# breakout.net
KiCad netlist of a schematic drawn in EAGLE
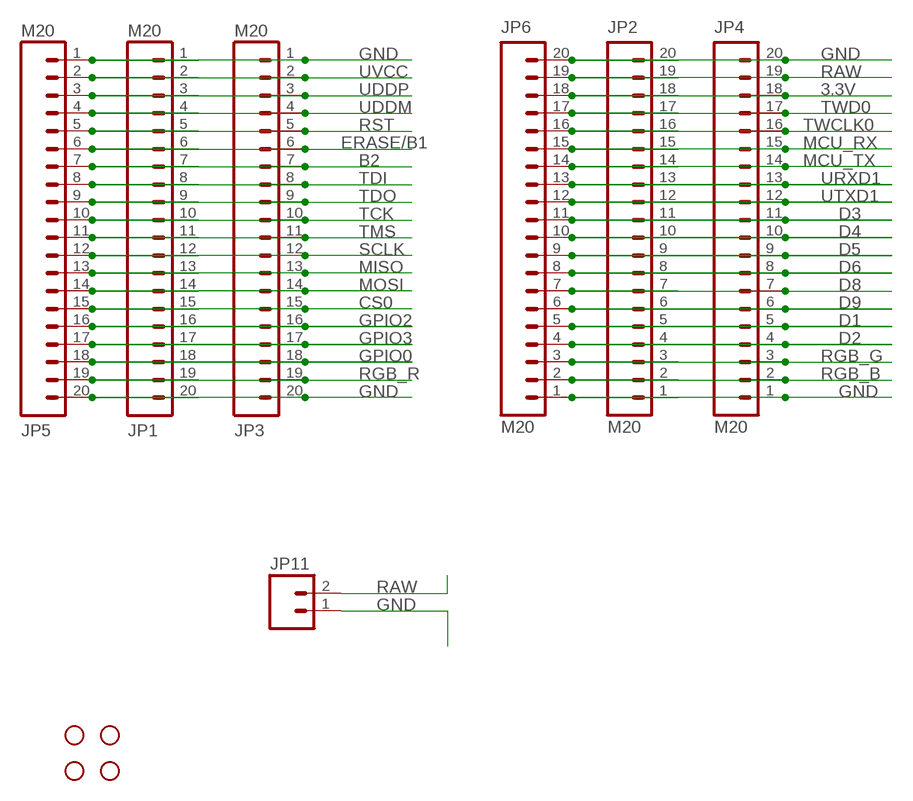
[diagram p0: schematic, sheet 1]

(export (version "E")
  (design (tool "Eeschema 10.0.6"))
  (components
    (comp (ref "JP1")
      (value "M20")
      (footprint "eagle-import:1X20")
      (libsource (lib "eagle-import") (part "M20"))
    )
    (comp (ref "JP2")
      (value "M20")
      (footprint "eagle-import:1X20")
      (libsource (lib "eagle-import") (part "M20"))
    )
    (comp (ref "JP3")
      (value "M20")
      (footprint "eagle-import:1X20")
      (libsource (lib "eagle-import") (part "M20"))
    )
    (comp (ref "JP4")
      (value "M20")
      (footprint "eagle-import:1X20")
      (libsource (lib "eagle-import") (part "M20"))
    )
    (comp (ref "JP5")
      (value "M20")
      (footprint "eagle-import:1X20")
      (libsource (lib "eagle-import") (part "M20"))
    )
    (comp (ref "JP6")
      (value "M20")
      (footprint "eagle-import:1X20")
      (libsource (lib "eagle-import") (part "M20"))
    )
    (comp (ref "JP7")
      (value "STAND-OFF")
      (footprint "eagle-import:STAND-OFF")
      (libsource (lib "eagle-import") (part "STAND-OFF"))
    )
    (comp (ref "JP8")
      (value "STAND-OFF")
      (footprint "eagle-import:STAND-OFF")
      (libsource (lib "eagle-import") (part "STAND-OFF"))
    )
    (comp (ref "JP9")
      (value "STAND-OFF")
      (footprint "eagle-import:STAND-OFF")
      (libsource (lib "eagle-import") (part "STAND-OFF"))
    )
    (comp (ref "JP10")
      (value "STAND-OFF")
      (footprint "eagle-import:STAND-OFF")
      (libsource (lib "eagle-import") (part "STAND-OFF"))
    )
    (comp (ref "JP11")
      (value "M02JST-PTH-2")
      (footprint "eagle-import:JST-2-PTH")
      (libsource (lib "eagle-import") (part "M02JST-PTH-2"))
    )
  )
  (nets
    (net (code "1") (name "3.3V") (class "Default")
      (node (ref "JP2") (pin "18") (pinfunction "18_18") (pintype "passive"))
      (node (ref "JP4") (pin "18") (pinfunction "18_18") (pintype "passive"))
      (node (ref "JP6") (pin "18") (pinfunction "18_18") (pintype "passive"))
    )
    (net (code "2") (name "B2") (class "Default")
      (node (ref "JP1") (pin "7") (pinfunction "7_7") (pintype "passive"))
      (node (ref "JP3") (pin "7") (pinfunction "7_7") (pintype "passive"))
      (node (ref "JP5") (pin "7") (pinfunction "7_7") (pintype "passive"))
    )
    (net (code "3") (name "CS0") (class "Default")
      (node (ref "JP1") (pin "15") (pinfunction "15_15") (pintype "passive"))
      (node (ref "JP3") (pin "15") (pinfunction "15_15") (pintype "passive"))
      (node (ref "JP5") (pin "15") (pinfunction "15_15") (pintype "passive"))
    )
    (net (code "4") (name "D1") (class "Default")
      (node (ref "JP2") (pin "5") (pinfunction "5_5") (pintype "passive"))
      (node (ref "JP4") (pin "5") (pinfunction "5_5") (pintype "passive"))
      (node (ref "JP6") (pin "5") (pinfunction "5_5") (pintype "passive"))
    )
    (net (code "5") (name "D2") (class "Default")
      (node (ref "JP2") (pin "4") (pinfunction "4_4") (pintype "passive"))
      (node (ref "JP4") (pin "4") (pinfunction "4_4") (pintype "passive"))
      (node (ref "JP6") (pin "4") (pinfunction "4_4") (pintype "passive"))
    )
    (net (code "6") (name "D3") (class "Default")
      (node (ref "JP2") (pin "11") (pinfunction "11_11") (pintype "passive"))
      (node (ref "JP4") (pin "11") (pinfunction "11_11") (pintype "passive"))
      (node (ref "JP6") (pin "11") (pinfunction "11_11") (pintype "passive"))
    )
    (net (code "7") (name "D4") (class "Default")
      (node (ref "JP2") (pin "10") (pinfunction "10_10") (pintype "passive"))
      (node (ref "JP4") (pin "10") (pinfunction "10_10") (pintype "passive"))
      (node (ref "JP6") (pin "10") (pinfunction "10_10") (pintype "passive"))
    )
    (net (code "8") (name "D5") (class "Default")
      (node (ref "JP2") (pin "9") (pinfunction "9_9") (pintype "passive"))
      (node (ref "JP4") (pin "9") (pinfunction "9_9") (pintype "passive"))
      (node (ref "JP6") (pin "9") (pinfunction "9_9") (pintype "passive"))
    )
    (net (code "9") (name "D6") (class "Default")
      (node (ref "JP2") (pin "8") (pinfunction "8_8") (pintype "passive"))
      (node (ref "JP4") (pin "8") (pinfunction "8_8") (pintype "passive"))
      (node (ref "JP6") (pin "8") (pinfunction "8_8") (pintype "passive"))
    )
    (net (code "10") (name "D8") (class "Default")
      (node (ref "JP2") (pin "7") (pinfunction "7_7") (pintype "passive"))
      (node (ref "JP4") (pin "7") (pinfunction "7_7") (pintype "passive"))
      (node (ref "JP6") (pin "7") (pinfunction "7_7") (pintype "passive"))
    )
    (net (code "11") (name "D9") (class "Default")
      (node (ref "JP2") (pin "6") (pinfunction "6_6") (pintype "passive"))
      (node (ref "JP4") (pin "6") (pinfunction "6_6") (pintype "passive"))
      (node (ref "JP6") (pin "6") (pinfunction "6_6") (pintype "passive"))
    )
    (net (code "12") (name "ERASE{slash}B1") (class "Default")
      (node (ref "JP1") (pin "6") (pinfunction "6_6") (pintype "passive"))
      (node (ref "JP3") (pin "6") (pinfunction "6_6") (pintype "passive"))
      (node (ref "JP5") (pin "6") (pinfunction "6_6") (pintype "passive"))
    )
    (net (code "13") (name "GND") (class "Default")
      (node (ref "JP1") (pin "1") (pinfunction "1_1") (pintype "passive"))
      (node (ref "JP1") (pin "20") (pinfunction "20_20") (pintype "passive"))
      (node (ref "JP11") (pin "1") (pinfunction "1_1") (pintype "passive"))
      (node (ref "JP2") (pin "1") (pinfunction "1_1") (pintype "passive"))
      (node (ref "JP2") (pin "20") (pinfunction "20_20") (pintype "passive"))
      (node (ref "JP3") (pin "1") (pinfunction "1_1") (pintype "passive"))
      (node (ref "JP3") (pin "20") (pinfunction "20_20") (pintype "passive"))
      (node (ref "JP4") (pin "1") (pinfunction "1_1") (pintype "passive"))
      (node (ref "JP4") (pin "20") (pinfunction "20_20") (pintype "passive"))
      (node (ref "JP5") (pin "1") (pinfunction "1_1") (pintype "passive"))
      (node (ref "JP5") (pin "20") (pinfunction "20_20") (pintype "passive"))
      (node (ref "JP6") (pin "1") (pinfunction "1_1") (pintype "passive"))
      (node (ref "JP6") (pin "20") (pinfunction "20_20") (pintype "passive"))
    )
    (net (code "14") (name "GPIO0") (class "Default")
      (node (ref "JP1") (pin "18") (pinfunction "18_18") (pintype "passive"))
      (node (ref "JP3") (pin "18") (pinfunction "18_18") (pintype "passive"))
      (node (ref "JP5") (pin "18") (pinfunction "18_18") (pintype "passive"))
    )
    (net (code "15") (name "GPIO2") (class "Default")
      (node (ref "JP1") (pin "16") (pinfunction "16_16") (pintype "passive"))
      (node (ref "JP3") (pin "16") (pinfunction "16_16") (pintype "passive"))
      (node (ref "JP5") (pin "16") (pinfunction "16_16") (pintype "passive"))
    )
    (net (code "16") (name "GPIO3") (class "Default")
      (node (ref "JP1") (pin "17") (pinfunction "17_17") (pintype "passive"))
      (node (ref "JP3") (pin "17") (pinfunction "17_17") (pintype "passive"))
      (node (ref "JP5") (pin "17") (pinfunction "17_17") (pintype "passive"))
    )
    (net (code "17") (name "MCU_RX") (class "Default")
      (node (ref "JP2") (pin "15") (pinfunction "15_15") (pintype "passive"))
      (node (ref "JP4") (pin "15") (pinfunction "15_15") (pintype "passive"))
      (node (ref "JP6") (pin "15") (pinfunction "15_15") (pintype "passive"))
    )
    (net (code "18") (name "MCU_TX") (class "Default")
      (node (ref "JP2") (pin "14") (pinfunction "14_14") (pintype "passive"))
      (node (ref "JP4") (pin "14") (pinfunction "14_14") (pintype "passive"))
      (node (ref "JP6") (pin "14") (pinfunction "14_14") (pintype "passive"))
    )
    (net (code "19") (name "MISO") (class "Default")
      (node (ref "JP1") (pin "13") (pinfunction "13_13") (pintype "passive"))
      (node (ref "JP3") (pin "13") (pinfunction "13_13") (pintype "passive"))
      (node (ref "JP5") (pin "13") (pinfunction "13_13") (pintype "passive"))
    )
    (net (code "20") (name "MOSI") (class "Default")
      (node (ref "JP1") (pin "14") (pinfunction "14_14") (pintype "passive"))
      (node (ref "JP3") (pin "14") (pinfunction "14_14") (pintype "passive"))
      (node (ref "JP5") (pin "14") (pinfunction "14_14") (pintype "passive"))
    )
    (net (code "21") (name "RAW") (class "Default")
      (node (ref "JP11") (pin "2") (pinfunction "2_2") (pintype "passive"))
      (node (ref "JP2") (pin "19") (pinfunction "19_19") (pintype "passive"))
      (node (ref "JP4") (pin "19") (pinfunction "19_19") (pintype "passive"))
      (node (ref "JP6") (pin "19") (pinfunction "19_19") (pintype "passive"))
    )
    (net (code "22") (name "RGB_B") (class "Default")
      (node (ref "JP2") (pin "2") (pinfunction "2_2") (pintype "passive"))
      (node (ref "JP4") (pin "2") (pinfunction "2_2") (pintype "passive"))
      (node (ref "JP6") (pin "2") (pinfunction "2_2") (pintype "passive"))
    )
    (net (code "23") (name "RGB_G") (class "Default")
      (node (ref "JP2") (pin "3") (pinfunction "3_3") (pintype "passive"))
      (node (ref "JP4") (pin "3") (pinfunction "3_3") (pintype "passive"))
      (node (ref "JP6") (pin "3") (pinfunction "3_3") (pintype "passive"))
    )
    (net (code "24") (name "RGB_R") (class "Default")
      (node (ref "JP1") (pin "19") (pinfunction "19_19") (pintype "passive"))
      (node (ref "JP3") (pin "19") (pinfunction "19_19") (pintype "passive"))
      (node (ref "JP5") (pin "19") (pinfunction "19_19") (pintype "passive"))
    )
    (net (code "25") (name "RST") (class "Default")
      (node (ref "JP1") (pin "5") (pinfunction "5_5") (pintype "passive"))
      (node (ref "JP3") (pin "5") (pinfunction "5_5") (pintype "passive"))
      (node (ref "JP5") (pin "5") (pinfunction "5_5") (pintype "passive"))
    )
    (net (code "26") (name "SCLK") (class "Default")
      (node (ref "JP1") (pin "12") (pinfunction "12_12") (pintype "passive"))
      (node (ref "JP3") (pin "12") (pinfunction "12_12") (pintype "passive"))
      (node (ref "JP5") (pin "12") (pinfunction "12_12") (pintype "passive"))
    )
    (net (code "27") (name "TCK") (class "Default")
      (node (ref "JP1") (pin "10") (pinfunction "10_10") (pintype "passive"))
      (node (ref "JP3") (pin "10") (pinfunction "10_10") (pintype "passive"))
      (node (ref "JP5") (pin "10") (pinfunction "10_10") (pintype "passive"))
    )
    (net (code "28") (name "TDI") (class "Default")
      (node (ref "JP1") (pin "8") (pinfunction "8_8") (pintype "passive"))
      (node (ref "JP3") (pin "8") (pinfunction "8_8") (pintype "passive"))
      (node (ref "JP5") (pin "8") (pinfunction "8_8") (pintype "passive"))
    )
    (net (code "29") (name "TDO") (class "Default")
      (node (ref "JP1") (pin "9") (pinfunction "9_9") (pintype "passive"))
      (node (ref "JP3") (pin "9") (pinfunction "9_9") (pintype "passive"))
      (node (ref "JP5") (pin "9") (pinfunction "9_9") (pintype "passive"))
    )
    (net (code "30") (name "TMS") (class "Default")
      (node (ref "JP1") (pin "11") (pinfunction "11_11") (pintype "passive"))
      (node (ref "JP3") (pin "11") (pinfunction "11_11") (pintype "passive"))
      (node (ref "JP5") (pin "11") (pinfunction "11_11") (pintype "passive"))
    )
    (net (code "31") (name "TWCLK0") (class "Default")
      (node (ref "JP2") (pin "16") (pinfunction "16_16") (pintype "passive"))
      (node (ref "JP4") (pin "16") (pinfunction "16_16") (pintype "passive"))
      (node (ref "JP6") (pin "16") (pinfunction "16_16") (pintype "passive"))
    )
    (net (code "32") (name "TWD0") (class "Default")
      (node (ref "JP2") (pin "17") (pinfunction "17_17") (pintype "passive"))
      (node (ref "JP4") (pin "17") (pinfunction "17_17") (pintype "passive"))
      (node (ref "JP6") (pin "17") (pinfunction "17_17") (pintype "passive"))
    )
    (net (code "33") (name "UDDM") (class "Default")
      (node (ref "JP1") (pin "4") (pinfunction "4_4") (pintype "passive"))
      (node (ref "JP3") (pin "4") (pinfunction "4_4") (pintype "passive"))
      (node (ref "JP5") (pin "4") (pinfunction "4_4") (pintype "passive"))
    )
    (net (code "34") (name "UDDP") (class "Default")
      (node (ref "JP1") (pin "3") (pinfunction "3_3") (pintype "passive"))
      (node (ref "JP3") (pin "3") (pinfunction "3_3") (pintype "passive"))
      (node (ref "JP5") (pin "3") (pinfunction "3_3") (pintype "passive"))
    )
    (net (code "35") (name "URXD1") (class "Default")
      (node (ref "JP2") (pin "13") (pinfunction "13_13") (pintype "passive"))
      (node (ref "JP4") (pin "13") (pinfunction "13_13") (pintype "passive"))
      (node (ref "JP6") (pin "13") (pinfunction "13_13") (pintype "passive"))
    )
    (net (code "36") (name "UTXD1") (class "Default")
      (node (ref "JP2") (pin "12") (pinfunction "12_12") (pintype "passive"))
      (node (ref "JP4") (pin "12") (pinfunction "12_12") (pintype "passive"))
      (node (ref "JP6") (pin "12") (pinfunction "12_12") (pintype "passive"))
    )
    (net (code "37") (name "UVCC") (class "Default")
      (node (ref "JP1") (pin "2") (pinfunction "2_2") (pintype "passive"))
      (node (ref "JP3") (pin "2") (pinfunction "2_2") (pintype "passive"))
      (node (ref "JP5") (pin "2") (pinfunction "2_2") (pintype "passive"))
    )
  )
)
